# GregTrack_BIG_SENS_v1_0.net
KiCad netlist of a schematic drawn in Altium Designer
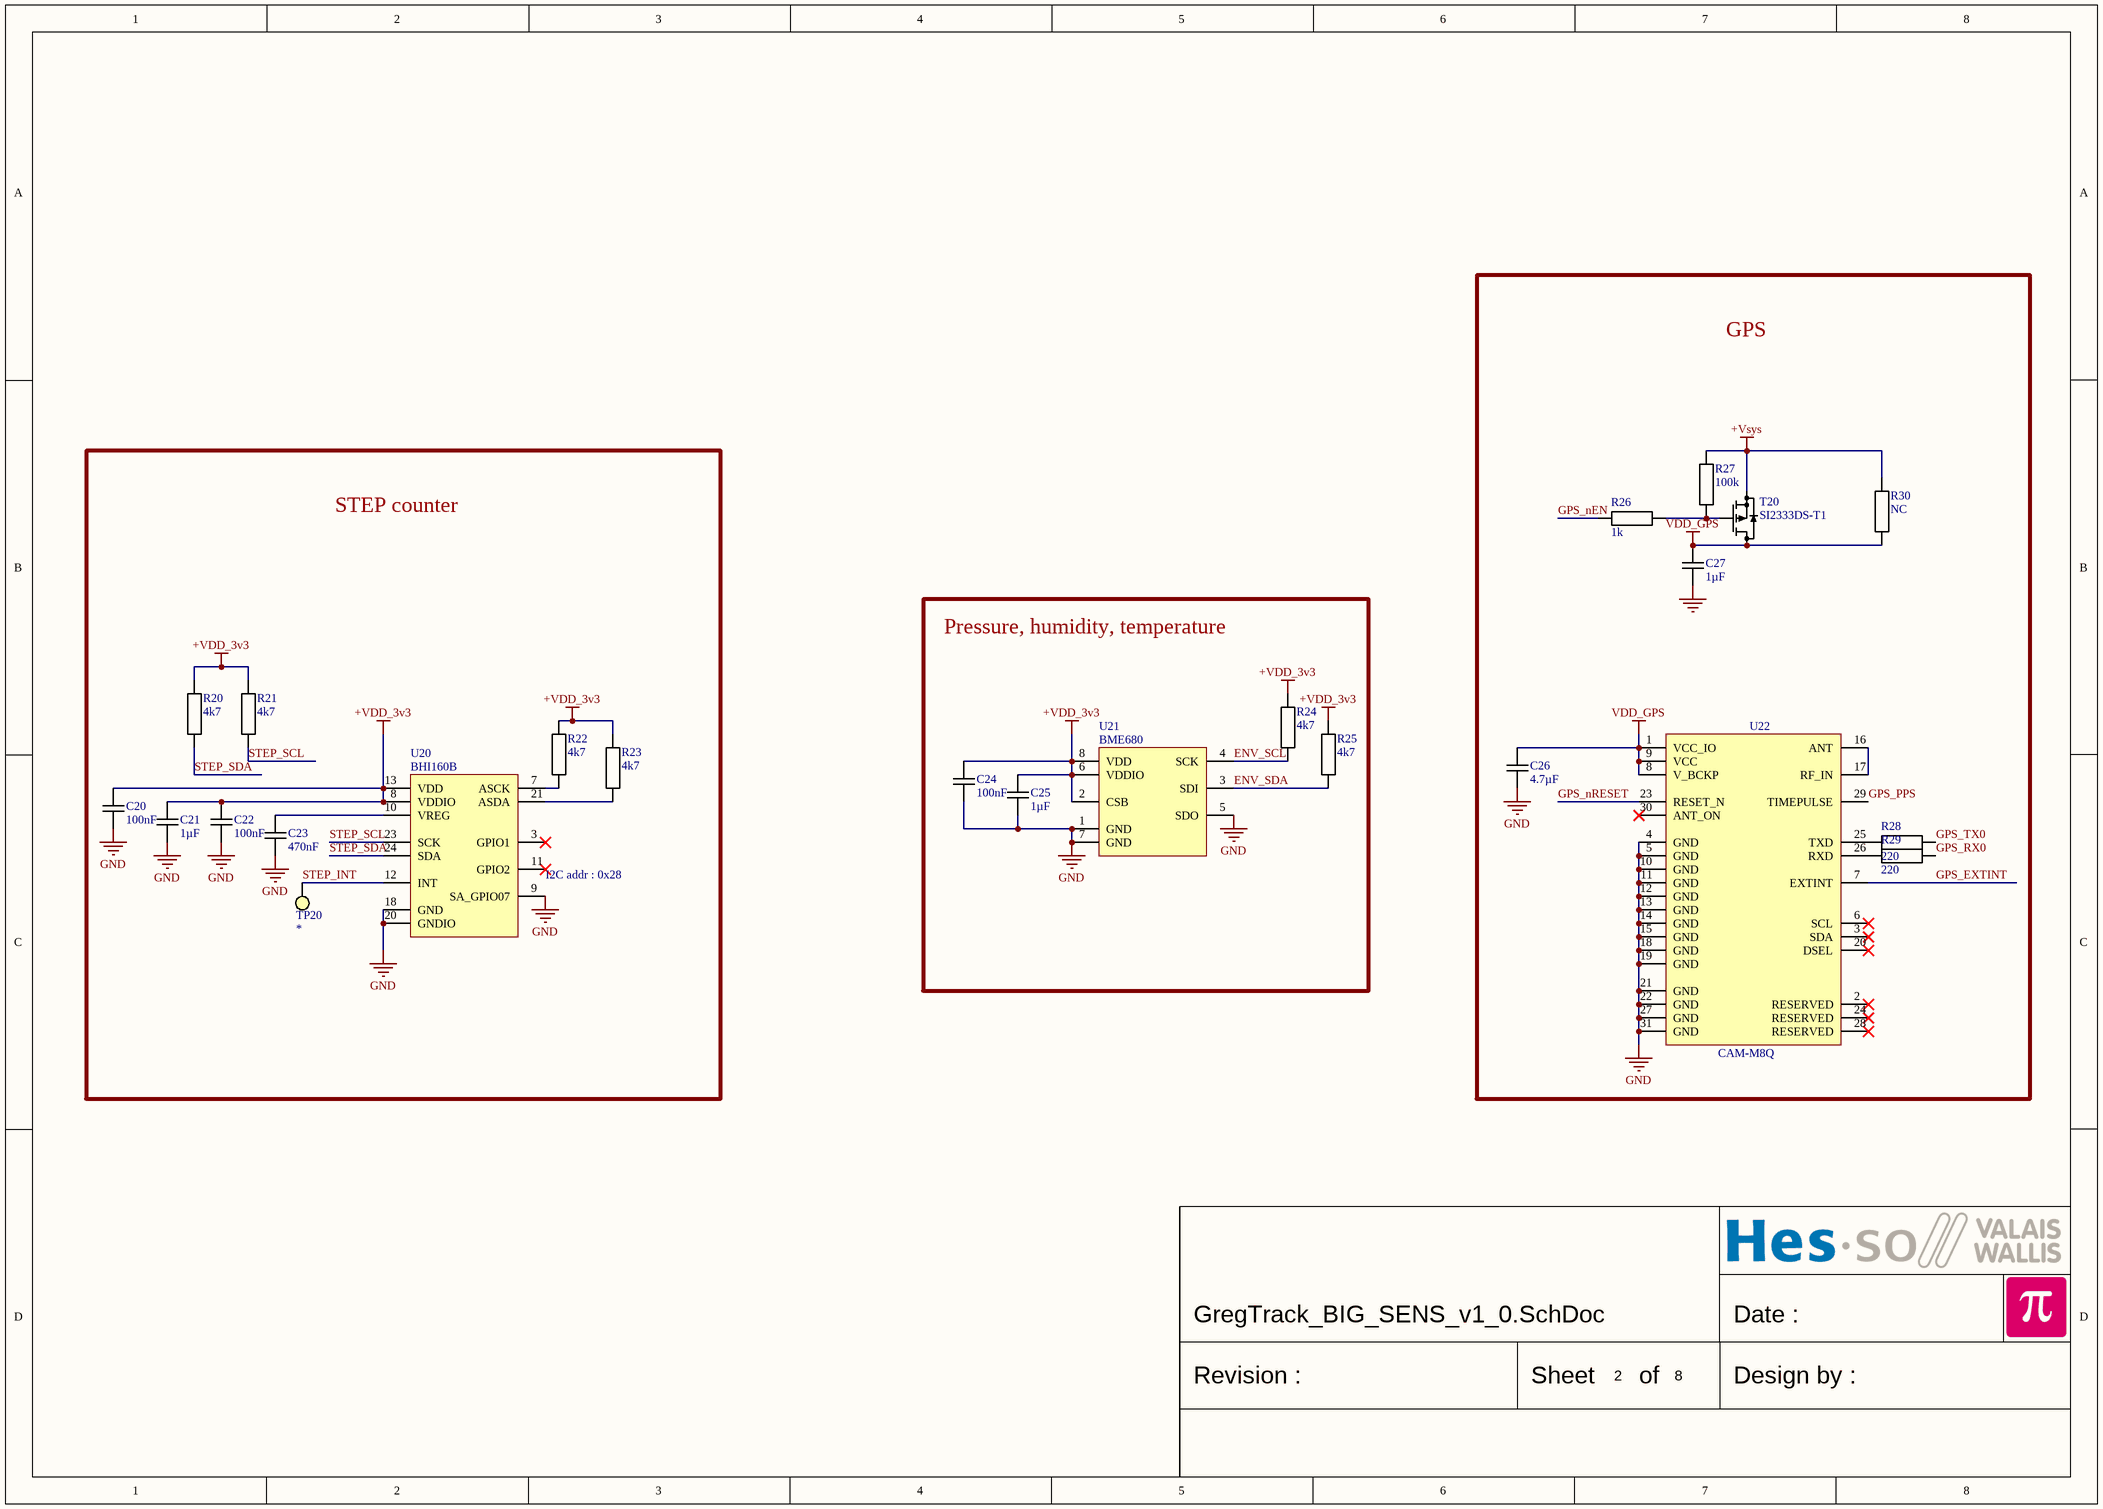
[diagram p0: GregTrack_BIG_SENS_v1_0.SchDoc]

(export (version "E")
  (design (tool "Eeschema 10.0.6"))
  (components
    (comp (ref "C20")
      (value "100nF")
      (footprint "CAPACITOR 1005 REFLOW")
      (description "Capacitor 1608 (0603)")
      (fields (field (name "TOLERANCE") "+/-20%") (field (name "VOLTAGE") "10V"))
      (libsource (lib "Capacitor") (part "Capacitor"))
    )
    (comp (ref "C21")
      (value "1µF")
      (footprint "CAPACITOR 1005 REFLOW")
      (description "Capacitor 1608 (0603)")
      (fields (field (name "TOLERANCE") "+/-20%") (field (name "VOLTAGE") "10V"))
      (libsource (lib "Capacitor") (part "Capacitor"))
    )
    (comp (ref "C22")
      (value "100nF")
      (footprint "CAPACITOR 1005 REFLOW")
      (description "Capacitor 1608 (0603)")
      (fields (field (name "TOLERANCE") "+/-20%") (field (name "VOLTAGE") "10V"))
      (libsource (lib "Capacitor") (part "Capacitor"))
    )
    (comp (ref "C23")
      (value "470nF")
      (footprint "CAPACITOR 1005 REFLOW")
      (description "Capacitor 1608 (0603)")
      (fields (field (name "TOLERANCE") "+/-20%") (field (name "VOLTAGE") "10V"))
      (libsource (lib "Capacitor") (part "Capacitor"))
    )
    (comp (ref "C24")
      (value "100nF")
      (footprint "CAPACITOR 1005 REFLOW")
      (description "Capacitor 1005")
      (fields (field (name "TOLERANCE") "+/-20%") (field (name "VOLTAGE") "10V"))
      (libsource (lib "Capacitor") (part "Capacitor"))
    )
    (comp (ref "C25")
      (value "1µF")
      (footprint "CAPACITOR 1005 REFLOW")
      (description "Capacitor 1005")
      (fields (field (name "TOLERANCE") "+/-20%") (field (name "VOLTAGE") "10V"))
      (libsource (lib "Capacitor") (part "Capacitor"))
    )
    (comp (ref "C26")
      (value "4.7µF")
      (footprint "CAPACITOR 1608 REFLOW")
      (description "Capacitor 1005")
      (fields (field (name "TOLERANCE") "20%") (field (name "VOLTAGE") "10V"))
      (libsource (lib "Capacitor") (part "Capacitor"))
    )
    (comp (ref "C27")
      (value "1µF")
      (footprint "CAPACITOR 1005 REFLOW")
      (description "Capacitor 1005")
      (fields (field (name "TOLERANCE") "20%") (field (name "VOLTAGE") "10V"))
      (libsource (lib "Capacitor") (part "Capacitor"))
    )
    (comp (ref "R20")
      (value "4k7")
      (footprint "RESISTOR 1005 REFLOW")
      (description "Resistor 1005")
      (fields (field (name "TOLERANCE") "1%"))
      (libsource (lib "Resistor") (part "Resistor"))
    )
    (comp (ref "R21")
      (value "4k7")
      (footprint "RESISTOR 1005 REFLOW")
      (description "Resistor 1005")
      (fields (field (name "TOLERANCE") "1%"))
      (libsource (lib "Resistor") (part "Resistor"))
    )
    (comp (ref "R22")
      (value "4k7")
      (footprint "RESISTOR 1005 REFLOW")
      (description "Resistor 1005")
      (fields (field (name "TOLERANCE") "1%"))
      (libsource (lib "Resistor") (part "Resistor"))
    )
    (comp (ref "R23")
      (value "4k7")
      (footprint "RESISTOR 1005 REFLOW")
      (description "Resistor 1005")
      (fields (field (name "TOLERANCE") "1%"))
      (libsource (lib "Resistor") (part "Resistor"))
    )
    (comp (ref "R24")
      (value "4k7")
      (footprint "RESISTOR 1005 REFLOW")
      (description "Resistor 1005")
      (fields (field (name "TOLERANCE") "1%"))
      (libsource (lib "Resistor") (part "Resistor"))
    )
    (comp (ref "R25")
      (value "4k7")
      (footprint "RESISTOR 1005 REFLOW")
      (description "Resistor 1005")
      (fields (field (name "TOLERANCE") "1%"))
      (libsource (lib "Resistor") (part "Resistor"))
    )
    (comp (ref "R26")
      (value "1k")
      (footprint "RESISTOR 1005 REFLOW")
      (description "Resistor 1005")
      (fields (field (name "TOLERANCE") "1%"))
      (libsource (lib "Resistor") (part "Resistor"))
    )
    (comp (ref "R27")
      (value "100k")
      (footprint "RESISTOR 1005 REFLOW")
      (description "Resistor 1005")
      (fields (field (name "TOLERANCE") "1%"))
      (libsource (lib "Resistor") (part "Resistor"))
    )
    (comp (ref "R28")
      (value "220")
      (footprint "RESISTOR 1005 REFLOW")
      (description "Resistor")
      (libsource (lib "Resistor") (part "Resistor"))
    )
    (comp (ref "R29")
      (value "220")
      (footprint "RESISTOR 1005 REFLOW")
      (description "Resistor")
      (libsource (lib "Resistor") (part "Resistor"))
    )
    (comp (ref "R30")
      (value "NC")
      (footprint "RESISTOR 1005 REFLOW")
      (description "Resistor 1005")
      (fields (field (name "TOLERANCE") "1%"))
      (libsource (lib "Resistor") (part "Resistor"))
    )
    (comp (ref "T20")
      (value "SI2333DS-T1")
      (footprint "SOT23 P0.95 C1.6x3.0 H1.3")
      (description "Generic MOS-P")
      (libsource (lib "Transistor") (part "MOS-P SOT23 G-S-D"))
    )
    (comp (ref "TP20")
      (value "*")
      (footprint "Pad D0.8")
      (description "Pad")
      (libsource (lib "Testpoint") (part "Pad"))
    )
    (comp (ref "U20")
      (value "BHI160B")
      (footprint "BHI160b")
      (description "Ultra low-power sensor hub incl. integrated IMU")
      (libsource (lib "Sensor") (part "BHI160B"))
    )
    (comp (ref "U21")
      (value "BME680")
      (footprint "BME680")
      (description "BME680Low power gas, pressure, temperature & humidity sensor")
      (libsource (lib "Sensor") (part "BME680"))
    )
    (comp (ref "U22")
      (value "CAM-M8Q")
      (footprint "CAM-M8Q")
      (description "u-blox M8 concurrent GNSS antenna modules")
      (libsource (lib "WirelessDevice") (part "CAM-M8Q"))
    )
  )
  (nets
    (net (code "1") (name "+VDD_3v3") (class "Default")
      (node (ref "C20") (pin "2") (pinfunction "2_2") (pintype "passive"))
      (node (ref "C21") (pin "2") (pinfunction "2_2") (pintype "passive"))
      (node (ref "C22") (pin "2") (pinfunction "2_2") (pintype "passive"))
      (node (ref "C24") (pin "2") (pinfunction "2_2") (pintype "passive"))
      (node (ref "C25") (pin "2") (pinfunction "2_2") (pintype "passive"))
      (node (ref "R20") (pin "1") (pinfunction "1_1") (pintype "passive"))
      (node (ref "R21") (pin "1") (pinfunction "1_1") (pintype "passive"))
      (node (ref "R22") (pin "2") (pinfunction "2_2") (pintype "passive"))
      (node (ref "R23") (pin "2") (pinfunction "2_2") (pintype "passive"))
      (node (ref "R24") (pin "1") (pinfunction "1_1") (pintype "passive"))
      (node (ref "R25") (pin "1") (pinfunction "1_1") (pintype "passive"))
      (node (ref "U20") (pin "13") (pinfunction "VDD_13") (pintype "passive"))
      (node (ref "U20") (pin "8") (pinfunction "VDDIO_8") (pintype "passive"))
      (node (ref "U21") (pin "2") (pinfunction "CSB_2") (pintype "passive"))
      (node (ref "U21") (pin "6") (pinfunction "VDDIO_6") (pintype "passive"))
      (node (ref "U21") (pin "8") (pinfunction "VDD_8") (pintype "passive"))
    )
    (net (code "2") (name "+Vsys") (class "Default")
      (node (ref "R27") (pin "1") (pinfunction "1_1") (pintype "passive"))
      (node (ref "R30") (pin "1") (pinfunction "1_1") (pintype "passive"))
      (node (ref "T20") (pin "2") (pinfunction "S_2") (pintype "passive"))
    )
    (net (code "3") (name "/ENV_SCL") (class "Default")
      (node (ref "R24") (pin "2") (pinfunction "2_2") (pintype "passive"))
      (node (ref "U21") (pin "4") (pinfunction "SCK_4") (pintype "passive"))
    )
    (net (code "4") (name "/ENV_SDA") (class "Default")
      (node (ref "R25") (pin "2") (pinfunction "2_2") (pintype "passive"))
      (node (ref "U21") (pin "3") (pinfunction "SDI_3") (pintype "passive"))
    )
    (net (code "5") (name "/GPS_EXTINT") (class "Default")
      (node (ref "U22") (pin "7") (pinfunction "EXTINT_7") (pintype "passive"))
    )
    (net (code "6") (name "/GPS_PPS") (class "Default")
      (node (ref "U22") (pin "29") (pinfunction "TIMEPULSE_29") (pintype "passive"))
    )
    (net (code "7") (name "/GPS_RX0") (class "Default")
      (node (ref "R29") (pin "2") (pinfunction "2_2") (pintype "passive"))
    )
    (net (code "8") (name "/GPS_TX0") (class "Default")
      (node (ref "R28") (pin "2") (pinfunction "2_2") (pintype "passive"))
    )
    (net (code "9") (name "/GPS_nEN") (class "Default")
      (node (ref "R26") (pin "1") (pinfunction "1_1") (pintype "passive"))
    )
    (net (code "10") (name "/GPS_nRESET") (class "Default")
      (node (ref "U22") (pin "23") (pinfunction "RESET_N_23") (pintype "passive"))
    )
    (net (code "11") (name "/STEP_INT") (class "Default")
      (node (ref "TP20") (pin "1") (pinfunction "1_1") (pintype "passive"))
      (node (ref "U20") (pin "12") (pinfunction "INT_12") (pintype "passive"))
    )
    (net (code "12") (name "/STEP_SCL") (class "Default")
      (node (ref "R21") (pin "2") (pinfunction "2_2") (pintype "passive"))
      (node (ref "U20") (pin "23") (pinfunction "SCK_23") (pintype "passive"))
    )
    (net (code "13") (name "/STEP_SDA") (class "Default")
      (node (ref "R20") (pin "2") (pinfunction "2_2") (pintype "passive"))
      (node (ref "U20") (pin "24") (pinfunction "SDA_24") (pintype "passive"))
    )
    (net (code "14") (name "GND") (class "Default")
      (node (ref "C20") (pin "1") (pinfunction "1_1") (pintype "passive"))
      (node (ref "C21") (pin "1") (pinfunction "1_1") (pintype "passive"))
      (node (ref "C22") (pin "1") (pinfunction "1_1") (pintype "passive"))
      (node (ref "C23") (pin "1") (pinfunction "1_1") (pintype "passive"))
      (node (ref "C24") (pin "1") (pinfunction "1_1") (pintype "passive"))
      (node (ref "C25") (pin "1") (pinfunction "1_1") (pintype "passive"))
      (node (ref "C26") (pin "2") (pinfunction "2_2") (pintype "passive"))
      (node (ref "C27") (pin "2") (pinfunction "2_2") (pintype "passive"))
      (node (ref "U20") (pin "18") (pinfunction "GND_18") (pintype "passive"))
      (node (ref "U20") (pin "20") (pinfunction "GNDIO_20") (pintype "passive"))
      (node (ref "U20") (pin "9") (pinfunction "SA_GPIO07_9") (pintype "passive"))
      (node (ref "U21") (pin "1") (pinfunction "GND_1") (pintype "passive"))
      (node (ref "U21") (pin "5") (pinfunction "SDO_5") (pintype "passive"))
      (node (ref "U21") (pin "7") (pinfunction "GND_7") (pintype "passive"))
      (node (ref "U22") (pin "10") (pinfunction "GND_10") (pintype "passive"))
      (node (ref "U22") (pin "11") (pinfunction "GND_11") (pintype "passive"))
      (node (ref "U22") (pin "12") (pinfunction "GND_12") (pintype "passive"))
      (node (ref "U22") (pin "13") (pinfunction "GND_13") (pintype "passive"))
      (node (ref "U22") (pin "14") (pinfunction "GND_14") (pintype "passive"))
      (node (ref "U22") (pin "15") (pinfunction "GND_15") (pintype "passive"))
      (node (ref "U22") (pin "18") (pinfunction "GND_18") (pintype "passive"))
      (node (ref "U22") (pin "19") (pinfunction "GND_19") (pintype "passive"))
      (node (ref "U22") (pin "21") (pinfunction "GND_21") (pintype "passive"))
      (node (ref "U22") (pin "22") (pinfunction "GND_22") (pintype "passive"))
      (node (ref "U22") (pin "27") (pinfunction "GND_27") (pintype "passive"))
      (node (ref "U22") (pin "31") (pinfunction "GND_31") (pintype "passive"))
      (node (ref "U22") (pin "4") (pinfunction "GND_4") (pintype "passive"))
      (node (ref "U22") (pin "5") (pinfunction "GND_5") (pintype "passive"))
    )
    (net (code "15") (name "Net-(T20-G)") (class "Default")
      (node (ref "R26") (pin "2") (pinfunction "2_2") (pintype "passive"))
      (node (ref "R27") (pin "2") (pinfunction "2_2") (pintype "passive"))
      (node (ref "T20") (pin "1") (pinfunction "G_1") (pintype "passive"))
    )
    (net (code "16") (name "Net-(U20-ASCK)") (class "Default")
      (node (ref "R22") (pin "1") (pinfunction "1_1") (pintype "passive"))
      (node (ref "U20") (pin "7") (pinfunction "ASCK_7") (pintype "passive"))
    )
    (net (code "17") (name "Net-(U20-ASDA)") (class "Default")
      (node (ref "R23") (pin "1") (pinfunction "1_1") (pintype "passive"))
      (node (ref "U20") (pin "21") (pinfunction "ASDA_21") (pintype "passive"))
    )
    (net (code "18") (name "Net-(U20-VREG)") (class "Default")
      (node (ref "C23") (pin "2") (pinfunction "2_2") (pintype "passive"))
      (node (ref "U20") (pin "10") (pinfunction "VREG_10") (pintype "passive"))
    )
    (net (code "19") (name "Net-(U22-ANT)") (class "Default")
      (node (ref "U22") (pin "16") (pinfunction "ANT_16") (pintype "passive"))
      (node (ref "U22") (pin "17") (pinfunction "RF_IN_17") (pintype "passive"))
    )
    (net (code "20") (name "Net-(U22-RXD)") (class "Default")
      (node (ref "R29") (pin "1") (pinfunction "1_1") (pintype "passive"))
      (node (ref "U22") (pin "26") (pinfunction "RXD_26") (pintype "passive"))
    )
    (net (code "21") (name "Net-(U22-TXD)") (class "Default")
      (node (ref "R28") (pin "1") (pinfunction "1_1") (pintype "passive"))
      (node (ref "U22") (pin "25") (pinfunction "TXD_25") (pintype "passive"))
    )
    (net (code "22") (name "VDD_GPS") (class "Default")
      (node (ref "C26") (pin "1") (pinfunction "1_1") (pintype "passive"))
      (node (ref "C27") (pin "1") (pinfunction "1_1") (pintype "passive"))
      (node (ref "R30") (pin "2") (pinfunction "2_2") (pintype "passive"))
      (node (ref "T20") (pin "3") (pinfunction "D_3") (pintype "passive"))
      (node (ref "U22") (pin "1") (pinfunction "VCC_IO_1") (pintype "passive"))
      (node (ref "U22") (pin "8") (pinfunction "V_BCKP_8") (pintype "passive"))
      (node (ref "U22") (pin "9") (pinfunction "VCC_9") (pintype "passive"))
    )
    (net (code "23") (name "unconnected-(U20-GPIO1-Pad3)") (class "Default")
      (node (ref "U20") (pin "3") (pinfunction "GPIO1_3") (pintype "passive+no_connect"))
    )
    (net (code "24") (name "unconnected-(U20-GPIO2-Pad11)") (class "Default")
      (node (ref "U20") (pin "11") (pinfunction "GPIO2_11") (pintype "passive+no_connect"))
    )
    (net (code "25") (name "unconnected-(U22-ANT_ON-Pad30)") (class "Default")
      (node (ref "U22") (pin "30") (pinfunction "ANT_ON_30") (pintype "passive+no_connect"))
    )
    (net (code "26") (name "unconnected-(U22-DSEL-Pad20)") (class "Default")
      (node (ref "U22") (pin "20") (pinfunction "DSEL_20") (pintype "passive+no_connect"))
    )
    (net (code "27") (name "unconnected-(U22-RESERVED-Pad2)") (class "Default")
      (node (ref "U22") (pin "2") (pinfunction "RESERVED_2") (pintype "passive+no_connect"))
    )
    (net (code "28") (name "unconnected-(U22-RESERVED-Pad24)") (class "Default")
      (node (ref "U22") (pin "24") (pinfunction "RESERVED_24") (pintype "passive+no_connect"))
    )
    (net (code "29") (name "unconnected-(U22-RESERVED-Pad28)") (class "Default")
      (node (ref "U22") (pin "28") (pinfunction "RESERVED_28") (pintype "passive+no_connect"))
    )
    (net (code "30") (name "unconnected-(U22-SCL-Pad6)") (class "Default")
      (node (ref "U22") (pin "6") (pinfunction "SCL_6") (pintype "passive+no_connect"))
    )
    (net (code "31") (name "unconnected-(U22-SDA-Pad3)") (class "Default")
      (node (ref "U22") (pin "3") (pinfunction "SDA_3") (pintype "passive+no_connect"))
    )
  )
)
